# 40_Controles.net
KiCad netlist of a schematic drawn in Altium Designer
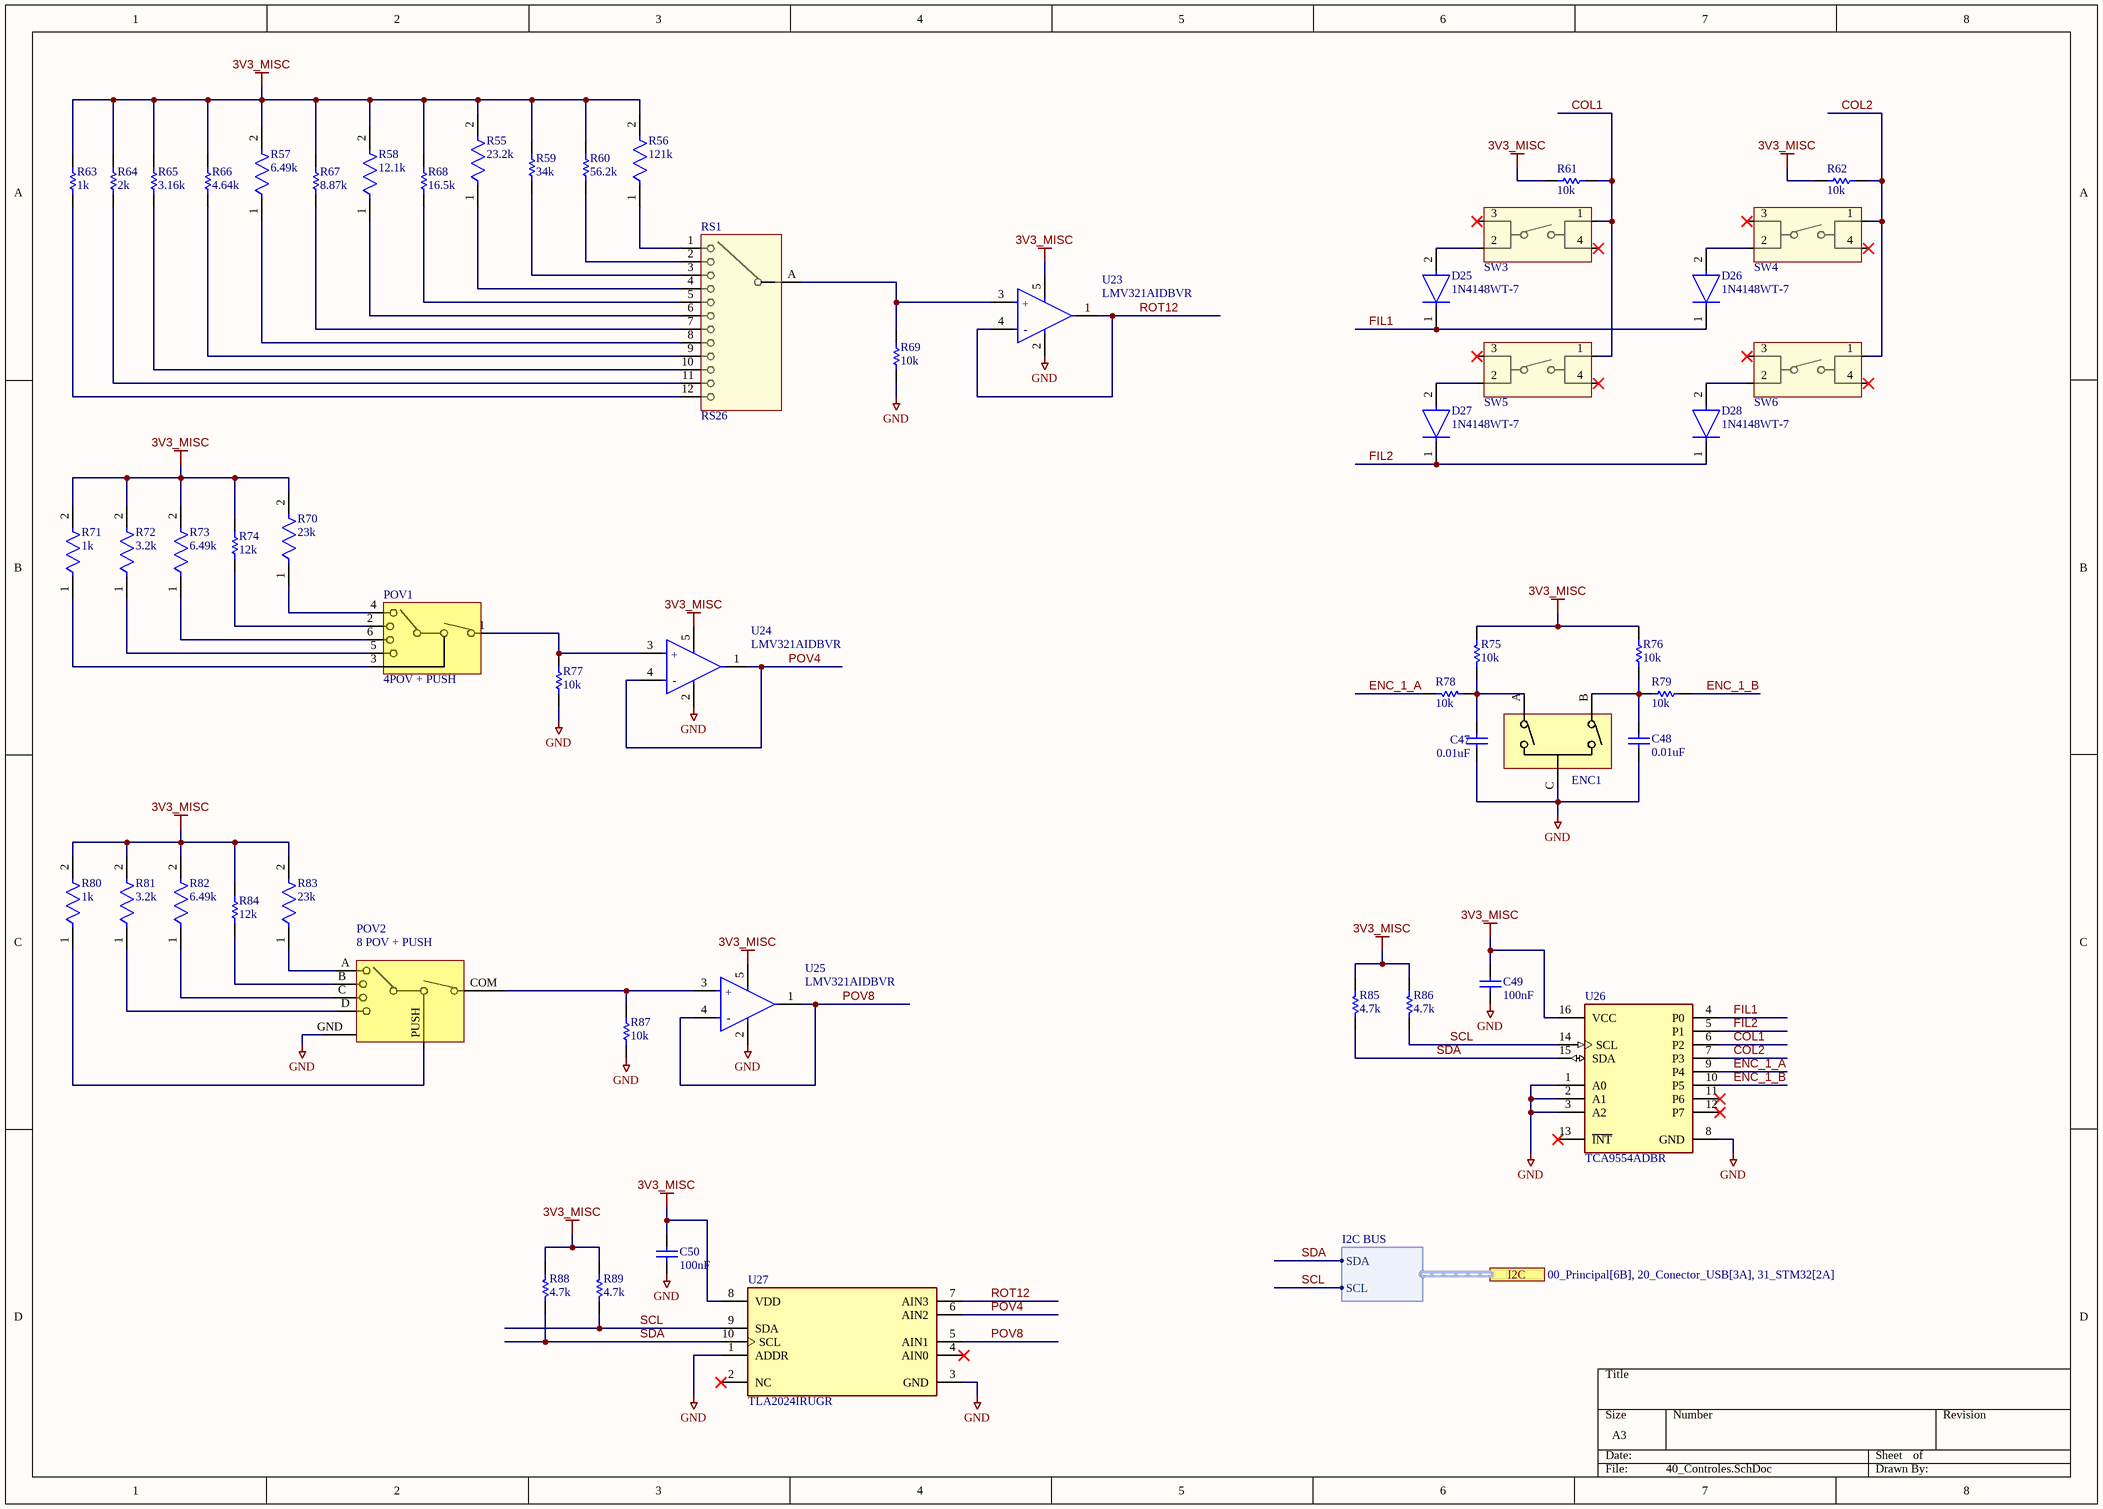
[diagram p0: 40_Controles.SchDoc]

(export (version "E")
  (design (tool "Eeschema 10.0.6"))
  (components
    (comp (ref "C47")
      (value "0.01uF")
      (footprint "CAPC1005X55X25LL05T10")
      (fields (field (name "MANUFACTURER") "Murata") (field (name "PART NUMBER") "GRM155R71E103KA01D"))
      (libsource (lib "Altium Content Vault") (part "CAP"))
    )
    (comp (ref "C48")
      (value "0.01uF")
      (footprint "CAPC1005X55X25LL05T10")
      (fields (field (name "MANUFACTURER") "Murata") (field (name "PART NUMBER") "GRM155R71E103KA01D"))
      (libsource (lib "Altium Content Vault") (part "CAP"))
    )
    (comp (ref "C49")
      (value "100nF")
      (footprint "CAPC1005X55X25NL05T05")
      (fields (field (name "MANUFACTURER") "Vitramon") (field (name "PART NUMBER") "VJ0402Y104KXJCW1BC"))
      (libsource (lib "Altium Content Vault") (part "CAP"))
    )
    (comp (ref "C50")
      (value "100nF")
      (footprint "CAPC1005X55X25NL05T05")
      (fields (field (name "MANUFACTURER") "Vitramon") (field (name "PART NUMBER") "VJ0402Y104KXJCW1BC"))
      (libsource (lib "Altium Content Vault") (part "CAP"))
    )
    (comp (ref "D25")
      (value "1N4148WT-7")
      (footprint "FP-SOD523-MFG")
      (description "DIODE GEN PURP 80V 125MA SOD523")
      (libsource (lib "Altium Content Vault") (part "d7152d700b627762746794eb795d46e"))
    )
    (comp (ref "D26")
      (value "1N4148WT-7")
      (footprint "FP-SOD523-MFG")
      (description "DIODE GEN PURP 80V 125MA SOD523")
      (libsource (lib "Altium Content Vault") (part "d7152d700b627762746794eb795d46e"))
    )
    (comp (ref "D27")
      (value "1N4148WT-7")
      (footprint "FP-SOD523-MFG")
      (description "DIODE GEN PURP 80V 125MA SOD523")
      (libsource (lib "Altium Content Vault") (part "d7152d700b627762746794eb795d46e"))
    )
    (comp (ref "D28")
      (value "1N4148WT-7")
      (footprint "FP-SOD523-MFG")
      (description "DIODE GEN PURP 80V 125MA SOD523")
      (libsource (lib "Altium Content Vault") (part "d7152d700b627762746794eb795d46e"))
    )
    (comp (ref "ENC1")
      (value "Encoder")
      (footprint "PEC09-2315F-N0015")
      (description "PEC09 PC Pin Quadrature (Incremental) 12 Mechanical Encoder 11.4mm 70C")
      (fields
        (field (name "MANUFACTURER") "Bourns")
        (field (name "MANUFACTURER PART NUMBER") "PEC09-2315F-N0015")
      )
      (libsource (lib "Esquemas") (part "PEC09-2315F-N0015"))
    )
    (comp (ref "POV1")
      (value "4POV + PUSH")
      (footprint "TSSJ 30")
      (description "SWITCH NAVIGATION 20MA 15V")
      (libsource (lib "Esquemas") (part "TSSJ 30"))
    )
    (comp (ref "POV2")
      (value "8 POV + PUSH")
      (footprint "RKJXM1015004")
      (description "8-directional Stick Switch (with Center-push Function) RKJXM Series")
      (libsource (lib "Esquemas") (part "RKJXM1015004"))
    )
    (comp (ref "R55")
      (value "23.2k")
      (footprint "FP-ERJ2R-MFG")
      (description "RES SMD 23.2K OHM 1% 1/10W 0402")
      (fields
        (field (name "MANUFACTURER PART NUMBER") "ERJ-2RKF2322X")
        (field (name "MANUFACTURER") "Panasonic")
      )
      (libsource (lib "Altium Content Vault") (part "1029c3af85768c4190bb7ad29bc67b5"))
    )
    (comp (ref "R56")
      (value "121k")
      (footprint "FP-ERJ2R-MFG")
      (description "RES SMD 121K OHM 1% 1/10W 0402")
      (fields
        (field (name "OCTOPART") "https://octopart.com/erj-2rkf1213x-panasonic-55420883")
        (field (name "MANUFACTURER") "Panasonic")
      )
      (libsource (lib "Altium Content Vault") (part "1029c3af85768c4190bb7ad29bc67b5"))
    )
    (comp (ref "R57")
      (value "6.49k")
      (footprint "FP-ERJ2RK-MFG")
      (fields (field (name "TOLERANCE") "1%"))
      (libsource (lib "Altium Content Vault") (part "1029c3af85768c4190bb7ad29bc67b5"))
    )
    (comp (ref "R58")
      (value "12.1k")
      (footprint "FP-ERJ2RK-IPC_C")
      (description "RES SMD 12.1K OHM 1% 1/10W 0402")
      (fields (field (name "TOLERANCE") "1%"))
      (libsource (lib "Altium Content Vault") (part "1029c3af85768c4190bb7ad29bc67b5"))
    )
    (comp (ref "R59")
      (value "34k")
      (footprint "RESC1005X40X25LL05T05")
      (fields (field (name "PART NUMBER") "ERJ-2RKF3402X") (field (name "MANUFACTURER") "Panasonic"))
      (libsource (lib "Altium Content Vault") (part "RES"))
    )
    (comp (ref "R60")
      (value "56.2k")
      (footprint "RESC1005X40X25LL05T05")
      (fields (field (name "PART NUMBER") "ERJ-2RKF5622X") (field (name "MANUFACTURER") "Panasonic"))
      (libsource (lib "Altium Content Vault") (part "RES"))
    )
    (comp (ref "R61")
      (value "10k")
      (footprint "RESC1005X40X25ML05T05")
      (fields (field (name "MANUFACTURER") "Panasonic") (field (name "PART NUMBER") "ERJ-2RHD1002X"))
      (libsource (lib "Altium Content Vault") (part "RES"))
    )
    (comp (ref "R62")
      (value "10k")
      (footprint "RESC1005X40X25ML05T05")
      (fields (field (name "MANUFACTURER") "Panasonic") (field (name "PART NUMBER") "ERJ-2RHD1002X"))
      (libsource (lib "Altium Content Vault") (part "RES"))
    )
    (comp (ref "R63")
      (value "1k")
      (footprint "RESC1005X40X25NL05T05")
      (description "Chip Resistor, 1 KOhm, +/- 1%, 100 mW, -55 to 155 degC, 0402 (1005 Metric), RoHS, Tape and Reel")
      (fields (field (name "PARTNUMBER") "ERJ-2RKF1001X") (field (name "MANUFACTURER") "Basic Passives"))
      (libsource (lib "Altium Content Vault") (part "RES-2"))
    )
    (comp (ref "R64")
      (value "2k")
      (footprint "RESC1005X40X25LL10T10")
      (fields (field (name "MANUFACTURER") "Panasonic") (field (name "PART NUMBER") "ERA-2AEB202X"))
      (libsource (lib "Altium Content Vault") (part "RES"))
    )
    (comp (ref "R65")
      (value "3.16k")
      (footprint "RESC1005X40X25ML05T05")
      (fields (field (name "MANUFACTURER") "Panasonic") (field (name "PART NUMBER") "ERJ-2RKF3161X"))
      (libsource (lib "Altium Content Vault") (part "RES"))
    )
    (comp (ref "R66")
      (value "4.64k")
      (footprint "RESC1005X40X25LL05T05")
      (fields (field (name "PART NUMBER") "ERJ-2RKF4641X") (field (name "MANUFACTURER") "Panasonic"))
      (libsource (lib "Altium Content Vault") (part "RES"))
    )
    (comp (ref "R67")
      (value "8.87k")
      (footprint "RESC1005X40X25NL05T05")
      (fields (field (name "PART NUMBER") "ERJ-2RKF8871X") (field (name "MANUFACTURER") "Panasonic"))
      (libsource (lib "Altium Content Vault") (part "RES"))
    )
    (comp (ref "R68")
      (value "16.5k")
      (footprint "RESC1005X40X25LL05T05")
      (fields (field (name "PART NUMBER") "ERJ-2RKF1652X") (field (name "MANUFACTURER") "Panasonic"))
      (libsource (lib "Altium Content Vault") (part "RES"))
    )
    (comp (ref "R69")
      (value "10k")
      (footprint "RESC1005X40X25ML05T05")
      (fields (field (name "MANUFACTURER") "Panasonic") (field (name "PART NUMBER") "ERJ-2RHD1002X"))
      (libsource (lib "Altium Content Vault") (part "RES"))
    )
    (comp (ref "R70")
      (value "23k")
      (footprint "FP-AC0402-MFG")
      (description "RES 23.2kΩ ±1% 0.063W 0402")
      (fields (field (name "TOLERANCE") "1%"))
      (libsource (lib "Altium Content Vault") (part "1029c3af85768c4190bb7ad29bc67b5"))
    )
    (comp (ref "R71")
      (value "1k")
      (footprint "FP-MCS0402-IPC_B")
      (description "RES SMD 1.2K OHM 1% 1/10W 0402")
      (fields (field (name "TOLERANCE") "0.1%"))
      (libsource (lib "Altium Content Vault") (part "1029c3af85768c4190bb7ad29bc67b5"))
    )
    (comp (ref "R72")
      (value "3.2k")
      (footprint "FP-RN73R1E-IPC_A")
      (description "3.2kΩ ±0.1% 0.063W, 1/16W Chip Resistor 0402 (1005 Metric) Moisture Resistant Thin Film")
      (libsource (lib "Altium Content Vault") (part "1029c3af85768c4190bb7ad29bc67b5"))
    )
    (comp (ref "R73")
      (value "6.49k")
      (footprint "FP-MCS0402-IPC_A")
      (description "RES SMD 1.2K OHM 1% 1/10W 0402")
      (fields (field (name "TOLERANCE") "1%"))
      (libsource (lib "Altium Content Vault") (part "1029c3af85768c4190bb7ad29bc67b5"))
    )
    (comp (ref "R74")
      (value "12k")
      (footprint "RESC0402(1005)_M")
      (description "12K 0.063W 5% 0402 (1005 Metric)  SMD")
      (fields (field (name "TOLERANCE") "5 %") (field (name "POWER") "0.063 W"))
      (libsource (lib "Altium Content Vault") (part "RES"))
    )
    (comp (ref "R75")
      (value "10k")
      (footprint "RESC1005X40X25ML05T05")
      (fields (field (name "MANUFACTURER") "Panasonic") (field (name "PART NUMBER") "ERJ-2RHD1002X"))
      (libsource (lib "Altium Content Vault") (part "RES"))
    )
    (comp (ref "R76")
      (value "10k")
      (footprint "RESC1005X40X25ML05T05")
      (fields (field (name "MANUFACTURER") "Panasonic") (field (name "PART NUMBER") "ERJ-2RHD1002X"))
      (libsource (lib "Altium Content Vault") (part "RES"))
    )
    (comp (ref "R77")
      (value "10k")
      (footprint "RESC1005X40X25ML05T05")
      (fields (field (name "MANUFACTURER") "Panasonic") (field (name "PART NUMBER") "ERJ-2RHD1002X"))
      (libsource (lib "Altium Content Vault") (part "RES"))
    )
    (comp (ref "R78")
      (value "10k")
      (footprint "RESC1005X40X25ML05T05")
      (fields (field (name "MANUFACTURER") "Panasonic") (field (name "PART NUMBER") "ERJ-2RHD1002X"))
      (libsource (lib "Altium Content Vault") (part "RES"))
    )
    (comp (ref "R79")
      (value "10k")
      (footprint "RESC1005X40X25ML05T05")
      (fields (field (name "MANUFACTURER") "Panasonic") (field (name "PART NUMBER") "ERJ-2RHD1002X"))
      (libsource (lib "Altium Content Vault") (part "RES"))
    )
    (comp (ref "R80")
      (value "1k")
      (footprint "FP-MCS0402-IPC_B")
      (description "RES SMD 1.2K OHM 1% 1/10W 0402")
      (fields (field (name "TOLERANCE") "0.1%"))
      (libsource (lib "Altium Content Vault") (part "1029c3af85768c4190bb7ad29bc67b5"))
    )
    (comp (ref "R81")
      (value "3.2k")
      (footprint "FP-RN73R1E-IPC_A")
      (description "3.2kΩ ±0.1% 0.063W, 1/16W Chip Resistor 0402 (1005 Metric) Moisture Resistant Thin Film")
      (libsource (lib "Altium Content Vault") (part "1029c3af85768c4190bb7ad29bc67b5"))
    )
    (comp (ref "R82")
      (value "6.49k")
      (footprint "FP-MCS0402-IPC_A")
      (description "RES SMD 1.2K OHM 1% 1/10W 0402")
      (fields (field (name "TOLERANCE") "1%"))
      (libsource (lib "Altium Content Vault") (part "1029c3af85768c4190bb7ad29bc67b5"))
    )
    (comp (ref "R83")
      (value "23k")
      (footprint "FP-AC0402-MFG")
      (description "RES 23.2kΩ ±1% 0.063W 0402")
      (fields (field (name "TOLERANCE") "1%"))
      (libsource (lib "Altium Content Vault") (part "1029c3af85768c4190bb7ad29bc67b5"))
    )
    (comp (ref "R84")
      (value "12k")
      (footprint "RESC0402(1005)_M")
      (description "12K 0.063W 5% 0402 (1005 Metric)  SMD")
      (fields (field (name "TOLERANCE") "5 %") (field (name "POWER") "0.063 W"))
      (libsource (lib "Altium Content Vault") (part "RES"))
    )
    (comp (ref "R85")
      (value "4.7k")
      (footprint "RESC1005X40X25ML05T10")
      (fields (field (name "MANUFACTURER") "Panasonic") (field (name "PART NUMBER") "ERJ-S02F4701X"))
      (libsource (lib "Altium Content Vault") (part "RES"))
    )
    (comp (ref "R86")
      (value "4.7k")
      (footprint "RESC1005X40X25ML05T10")
      (fields (field (name "MANUFACTURER") "Panasonic") (field (name "PART NUMBER") "ERJ-S02F4701X"))
      (libsource (lib "Altium Content Vault") (part "RES"))
    )
    (comp (ref "R87")
      (value "10k")
      (footprint "RESC1005X40X25ML05T05")
      (fields (field (name "MANUFACTURER") "Panasonic") (field (name "PART NUMBER") "ERJ-2RHD1002X"))
      (libsource (lib "Altium Content Vault") (part "RES"))
    )
    (comp (ref "R88")
      (value "4.7k")
      (footprint "RESC1005X40X25ML05T10")
      (fields (field (name "MANUFACTURER") "Panasonic") (field (name "PART NUMBER") "ERJ-S02F4701X"))
      (libsource (lib "Altium Content Vault") (part "RES"))
    )
    (comp (ref "R89")
      (value "4.7k")
      (footprint "RESC1005X40X25ML05T10")
      (fields (field (name "MANUFACTURER") "Panasonic") (field (name "PART NUMBER") "ERJ-S02F4701X"))
      (libsource (lib "Altium Content Vault") (part "RES"))
    )
    (comp (ref "RS1")
      (value "RS26")
      (footprint "RS26")
      (description "RS26 Rotary Type Band Switch Position Switch")
      (libsource (lib "Esquemas") (part "RS26 Rotary Coder"))
    )
    (comp (ref "SW3")
      (value "KSC441G70SHLFSPF")
      (footprint "KSC441G 70SH LFS PF")
      (description "Switch Tactile N.O. SPST Button 1VA 32VDC 50mA 4N Gull Wing SMD T/R")
      (fields (field (name "MANUFACTURER") "C&K Components"))
      (libsource (lib "Esquemas") (part "KSC441G70SHLFSPF"))
    )
    (comp (ref "SW4")
      (value "KSC441G70SHLFSPF")
      (footprint "KSC441G 70SH LFS PF")
      (description "Switch Tactile N.O. SPST Button 1VA 32VDC 50mA 4N Gull Wing SMD T/R")
      (fields (field (name "MANUFACTURER") "C&K Components"))
      (libsource (lib "Esquemas") (part "KSC441G70SHLFSPF"))
    )
    (comp (ref "SW5")
      (value "KSC441G70SHLFSPF")
      (footprint "KSC441G 70SH LFS PF")
      (description "Switch Tactile N.O. SPST Button 1VA 32VDC 50mA 4N Gull Wing SMD T/R")
      (fields (field (name "MANUFACTURER") "C&K Components"))
      (libsource (lib "Esquemas") (part "KSC441G70SHLFSPF"))
    )
    (comp (ref "SW6")
      (value "KSC441G70SHLFSPF")
      (footprint "KSC441G 70SH LFS PF")
      (description "Switch Tactile N.O. SPST Button 1VA 32VDC 50mA 4N Gull Wing SMD T/R")
      (fields (field (name "MANUFACTURER") "C&K Components"))
      (libsource (lib "Esquemas") (part "KSC441G70SHLFSPF"))
    )
    (comp (ref "U23")
      (value "LMV321AIDBVR")
      (footprint "FP-DBV0005A-MFG")
      (description "IC OPAMP GP 1 CIRCUIT SOT23-5")
      (libsource (lib "Altium Content Vault") (part "1dcd28e651784f0a5a8ed6f8452eeff"))
    )
    (comp (ref "U24")
      (value "LMV321AIDBVR")
      (footprint "FP-DBV0005A-MFG")
      (description "IC OPAMP GP 1 CIRCUIT SOT23-5")
      (libsource (lib "Altium Content Vault") (part "1dcd28e651784f0a5a8ed6f8452eeff"))
    )
    (comp (ref "U25")
      (value "LMV321AIDBVR")
      (footprint "FP-DBV0005A-MFG")
      (description "IC OPAMP GP 1 CIRCUIT SOT23-5")
      (libsource (lib "Altium Content Vault") (part "1dcd28e651784f0a5a8ed6f8452eeff"))
    )
    (comp (ref "U26")
      (value "TCA9554ADBR")
      (footprint "FP-DB0016A-MFG")
      (description "IC SMBUS I/O EXPANDER I2C 16SSOP")
      (libsource (lib "Altium Content Vault") (part "5b8be9e160fc3a406f4826644c42a9b"))
    )
    (comp (ref "U27")
      (value "TLA2024IRUGR")
      (footprint "FP-RUG0010A-MFG")
      (description "IC ADC 12BIT SIGMA-DELTA 10X2QFN")
      (libsource (lib "Altium Content Vault") (part "eb3f1feaf096e0a4fed058628c4118d"))
    )
  )
  (nets
    (net (code "3") (name "/COL1") (class "Default")
      (node (ref "R61") (pin "1") (pinfunction "1_1") (pintype "passive"))
      (node (ref "SW3") (pin "1") (pinfunction "0_1") (pintype "passive"))
      (node (ref "SW5") (pin "1") (pinfunction "0_1") (pintype "passive"))
      (node (ref "U26") (pin "6") (pinfunction "P2_6") (pintype "passive"))
    )
    (net (code "4") (name "/COL2") (class "Default")
      (node (ref "R62") (pin "1") (pinfunction "1_1") (pintype "passive"))
      (node (ref "SW4") (pin "1") (pinfunction "0_1") (pintype "passive"))
      (node (ref "SW6") (pin "1") (pinfunction "0_1") (pintype "passive"))
      (node (ref "U26") (pin "7") (pinfunction "P3_7") (pintype "passive"))
    )
    (net (code "5") (name "/ENC_1_A") (class "Default")
      (node (ref "R78") (pin "1") (pinfunction "1_1") (pintype "passive"))
      (node (ref "U26") (pin "9") (pinfunction "P4_9") (pintype "passive"))
    )
    (net (code "6") (name "/ENC_1_B") (class "Default")
      (node (ref "R79") (pin "1") (pinfunction "1_1") (pintype "passive"))
      (node (ref "U26") (pin "10") (pinfunction "P5_10") (pintype "passive"))
    )
    (net (code "7") (name "/FIL1") (class "Default")
      (node (ref "D25") (pin "1") (pinfunction "C_1") (pintype "passive"))
      (node (ref "D26") (pin "1") (pinfunction "C_1") (pintype "passive"))
      (node (ref "U26") (pin "4") (pinfunction "P0_4") (pintype "passive"))
    )
    (net (code "8") (name "/FIL2") (class "Default")
      (node (ref "D27") (pin "1") (pinfunction "C_1") (pintype "passive"))
      (node (ref "D28") (pin "1") (pinfunction "C_1") (pintype "passive"))
      (node (ref "U26") (pin "5") (pinfunction "P1_5") (pintype "passive"))
    )
    (net (code "9") (name "/POV4") (class "Default")
      (node (ref "U24") (pin "1") (pinfunction "OUT_1") (pintype "passive"))
      (node (ref "U24") (pin "4") (pinfunction "-IN_4") (pintype "tri_state"))
      (node (ref "U27") (pin "6") (pinfunction "AIN2_6") (pintype "passive"))
    )
    (net (code "10") (name "/POV8") (class "Default")
      (node (ref "U25") (pin "1") (pinfunction "OUT_1") (pintype "passive"))
      (node (ref "U25") (pin "4") (pinfunction "-IN_4") (pintype "tri_state"))
      (node (ref "U27") (pin "5") (pinfunction "AIN1_5") (pintype "passive"))
    )
    (net (code "11") (name "/ROT12") (class "Default")
      (node (ref "U23") (pin "1") (pinfunction "OUT_1") (pintype "passive"))
      (node (ref "U23") (pin "4") (pinfunction "-IN_4") (pintype "tri_state"))
      (node (ref "U27") (pin "7") (pinfunction "AIN3_7") (pintype "passive"))
    )
    (net (code "12") (name "/SCL") (class "Default")
      (node (ref "R86") (pin "1") (pinfunction "1_1") (pintype "passive"))
      (node (ref "R89") (pin "1") (pinfunction "1_1") (pintype "passive"))
      (node (ref "U26") (pin "14") (pinfunction "SCL_14") (pintype "input"))
      (node (ref "U27") (pin "9") (pinfunction "SDA_9") (pintype "passive"))
    )
    (net (code "13") (name "/SDA") (class "Default")
      (node (ref "R85") (pin "1") (pinfunction "1_1") (pintype "passive"))
      (node (ref "R88") (pin "1") (pinfunction "1_1") (pintype "passive"))
      (node (ref "U26") (pin "15") (pinfunction "SDA_15") (pintype "bidirectional"))
      (node (ref "U27") (pin "10") (pinfunction "SCL_10") (pintype "passive"))
    )
    (net (code "15") (name "3V3_MISC") (class "Default")
      (node (ref "C49") (pin "2") (pinfunction "2_2") (pintype "passive"))
      (node (ref "C50") (pin "2") (pinfunction "2_2") (pintype "passive"))
      (node (ref "R55") (pin "2") (pinfunction "2_2") (pintype "passive"))
      (node (ref "R56") (pin "2") (pinfunction "2_2") (pintype "passive"))
      (node (ref "R57") (pin "2") (pinfunction "2_2") (pintype "passive"))
      (node (ref "R58") (pin "2") (pinfunction "2_2") (pintype "passive"))
      (node (ref "R59") (pin "2") (pinfunction "2_2") (pintype "passive"))
      (node (ref "R60") (pin "2") (pinfunction "2_2") (pintype "passive"))
      (node (ref "R61") (pin "2") (pinfunction "2_2") (pintype "passive"))
      (node (ref "R62") (pin "2") (pinfunction "2_2") (pintype "passive"))
      (node (ref "R63") (pin "2") (pinfunction "2_2") (pintype "passive"))
      (node (ref "R64") (pin "2") (pinfunction "2_2") (pintype "passive"))
      (node (ref "R65") (pin "2") (pinfunction "2_2") (pintype "passive"))
      (node (ref "R66") (pin "2") (pinfunction "2_2") (pintype "passive"))
      (node (ref "R67") (pin "2") (pinfunction "2_2") (pintype "passive"))
      (node (ref "R68") (pin "2") (pinfunction "2_2") (pintype "passive"))
      (node (ref "R70") (pin "2") (pinfunction "2_2") (pintype "passive"))
      (node (ref "R71") (pin "2") (pinfunction "2_2") (pintype "passive"))
      (node (ref "R72") (pin "2") (pinfunction "2_2") (pintype "passive"))
      (node (ref "R73") (pin "2") (pinfunction "2_2") (pintype "passive"))
      (node (ref "R74") (pin "2") (pinfunction "2_2") (pintype "passive"))
      (node (ref "R75") (pin "1") (pinfunction "1_1") (pintype "passive"))
      (node (ref "R76") (pin "1") (pinfunction "1_1") (pintype "passive"))
      (node (ref "R80") (pin "2") (pinfunction "2_2") (pintype "passive"))
      (node (ref "R81") (pin "2") (pinfunction "2_2") (pintype "passive"))
      (node (ref "R82") (pin "2") (pinfunction "2_2") (pintype "passive"))
      (node (ref "R83") (pin "2") (pinfunction "2_2") (pintype "passive"))
      (node (ref "R84") (pin "2") (pinfunction "2_2") (pintype "passive"))
      (node (ref "R85") (pin "2") (pinfunction "2_2") (pintype "passive"))
      (node (ref "R86") (pin "2") (pinfunction "2_2") (pintype "passive"))
      (node (ref "R88") (pin "2") (pinfunction "2_2") (pintype "passive"))
      (node (ref "R89") (pin "2") (pinfunction "2_2") (pintype "passive"))
      (node (ref "U23") (pin "5") (pinfunction "V+_5") (pintype "passive"))
      (node (ref "U24") (pin "5") (pinfunction "V+_5") (pintype "passive"))
      (node (ref "U25") (pin "5") (pinfunction "V+_5") (pintype "passive"))
      (node (ref "U26") (pin "16") (pinfunction "VCC_16") (pintype "passive"))
      (node (ref "U27") (pin "8") (pinfunction "VDD_8") (pintype "passive"))
    )
    (net (code "16") (name "GND") (class "Default")
      (node (ref "C47") (pin "1") (pinfunction "1_1") (pintype "passive"))
      (node (ref "C48") (pin "1") (pinfunction "1_1") (pintype "passive"))
      (node (ref "C49") (pin "1") (pinfunction "1_1") (pintype "passive"))
      (node (ref "C50") (pin "1") (pinfunction "1_1") (pintype "passive"))
      (node (ref "ENC1") (pin "C") (pinfunction "COM_C") (pintype "passive"))
      (node (ref "POV2") (pin "GND") (pinfunction "GND_GND") (pintype "passive"))
      (node (ref "R69") (pin "1") (pinfunction "1_1") (pintype "passive"))
      (node (ref "R77") (pin "1") (pinfunction "1_1") (pintype "passive"))
      (node (ref "R87") (pin "1") (pinfunction "1_1") (pintype "passive"))
      (node (ref "U23") (pin "2") (pinfunction "V-_2") (pintype "passive"))
      (node (ref "U24") (pin "2") (pinfunction "V-_2") (pintype "passive"))
      (node (ref "U25") (pin "2") (pinfunction "V-_2") (pintype "passive"))
      (node (ref "U26") (pin "1") (pinfunction "A0_1") (pintype "passive"))
      (node (ref "U26") (pin "2") (pinfunction "A1_2") (pintype "passive"))
      (node (ref "U26") (pin "3") (pinfunction "A2_3") (pintype "passive"))
      (node (ref "U26") (pin "8") (pinfunction "GND_8") (pintype "passive"))
      (node (ref "U27") (pin "1") (pinfunction "ADDR_1") (pintype "passive"))
      (node (ref "U27") (pin "3") (pinfunction "GND_3") (pintype "passive"))
    )
    (net (code "17") (name "Net-(C47-Pad2)") (class "Default")
      (node (ref "C47") (pin "2") (pinfunction "2_2") (pintype "passive"))
      (node (ref "ENC1") (pin "A") (pinfunction "COM_A") (pintype "passive"))
      (node (ref "R75") (pin "2") (pinfunction "2_2") (pintype "passive"))
      (node (ref "R78") (pin "2") (pinfunction "2_2") (pintype "passive"))
    )
    (net (code "18") (name "Net-(C48-Pad2)") (class "Default")
      (node (ref "C48") (pin "2") (pinfunction "2_2") (pintype "passive"))
      (node (ref "ENC1") (pin "B") (pinfunction "COM_B") (pintype "passive"))
      (node (ref "R76") (pin "2") (pinfunction "2_2") (pintype "passive"))
      (node (ref "R79") (pin "2") (pinfunction "2_2") (pintype "passive"))
    )
    (net (code "19") (name "Net-(D25-A)") (class "Default")
      (node (ref "D25") (pin "2") (pinfunction "A_2") (pintype "passive"))
      (node (ref "SW3") (pin "2") (pinfunction "1_2") (pintype "passive"))
    )
    (net (code "20") (name "Net-(D26-A)") (class "Default")
      (node (ref "D26") (pin "2") (pinfunction "A_2") (pintype "passive"))
      (node (ref "SW4") (pin "2") (pinfunction "1_2") (pintype "passive"))
    )
    (net (code "21") (name "Net-(D27-A)") (class "Default")
      (node (ref "D27") (pin "2") (pinfunction "A_2") (pintype "passive"))
      (node (ref "SW5") (pin "2") (pinfunction "1_2") (pintype "passive"))
    )
    (net (code "22") (name "Net-(D28-A)") (class "Default")
      (node (ref "D28") (pin "2") (pinfunction "A_2") (pintype "passive"))
      (node (ref "SW6") (pin "2") (pinfunction "1_2") (pintype "passive"))
    )
    (net (code "23") (name "Net-(POV1-4)") (class "Default")
      (node (ref "POV1") (pin "3") (pinfunction "4_3") (pintype "passive"))
      (node (ref "R71") (pin "1") (pinfunction "1_1") (pintype "passive"))
    )
    (net (code "24") (name "Net-(POV1-COM)") (class "Default")
      (node (ref "POV1") (pin "1") (pinfunction "COM_1") (pintype "passive"))
      (node (ref "R77") (pin "2") (pinfunction "2_2") (pintype "passive"))
      (node (ref "U24") (pin "3") (pinfunction "+IN_3") (pintype "tri_state"))
    )
    (net (code "25") (name "Net-(POV1-DIRA)") (class "Default")
      (node (ref "POV1") (pin "4") (pinfunction "DIRA_4") (pintype "passive"))
      (node (ref "R70") (pin "1") (pinfunction "1_1") (pintype "passive"))
    )
    (net (code "26") (name "Net-(POV1-DIRB)") (class "Default")
      (node (ref "POV1") (pin "2") (pinfunction "DIRB_2") (pintype "passive"))
      (node (ref "R74") (pin "1") (pinfunction "1_1") (pintype "passive"))
    )
    (net (code "27") (name "Net-(POV1-DIRC)") (class "Default")
      (node (ref "POV1") (pin "6") (pinfunction "DIRC_6") (pintype "passive"))
      (node (ref "R73") (pin "1") (pinfunction "1_1") (pintype "passive"))
    )
    (net (code "28") (name "Net-(POV1-DIRD)") (class "Default")
      (node (ref "POV1") (pin "5") (pinfunction "DIRD_5") (pintype "passive"))
      (node (ref "R72") (pin "1") (pinfunction "1_1") (pintype "passive"))
    )
    (net (code "29") (name "Net-(POV2-DIRA)") (class "Default")
      (node (ref "POV2") (pin "A") (pinfunction "DIRA_A") (pintype "passive"))
      (node (ref "R83") (pin "1") (pinfunction "1_1") (pintype "passive"))
    )
    (net (code "30") (name "Net-(POV2-DIRB)") (class "Default")
      (node (ref "POV2") (pin "B") (pinfunction "DIRB_B") (pintype "passive"))
      (node (ref "R84") (pin "1") (pinfunction "1_1") (pintype "passive"))
    )
    (net (code "31") (name "Net-(POV2-DIRC)") (class "Default")
      (node (ref "POV2") (pin "C") (pinfunction "DIRC_C") (pintype "passive"))
      (node (ref "R82") (pin "1") (pinfunction "1_1") (pintype "passive"))
    )
    (net (code "32") (name "Net-(POV2-DIRD)") (class "Default")
      (node (ref "POV2") (pin "D") (pinfunction "DIRD_D") (pintype "passive"))
      (node (ref "R81") (pin "1") (pinfunction "1_1") (pintype "passive"))
    )
    (net (code "33") (name "Net-(POV2-PadPUSH)") (class "Default")
      (node (ref "POV2") (pin "PUSH") (pinfunction "PUSH_PUSH") (pintype "passive"))
      (node (ref "R80") (pin "1") (pinfunction "1_1") (pintype "passive"))
    )
    (net (code "34") (name "Net-(R55-Pad1)") (class "Default")
      (node (ref "R55") (pin "1") (pinfunction "1_1") (pintype "passive"))
      (node (ref "RS1") (pin "4") (pinfunction "A_4") (pintype "passive"))
    )
    (net (code "35") (name "Net-(R56-Pad1)") (class "Default")
      (node (ref "R56") (pin "1") (pinfunction "1_1") (pintype "passive"))
      (node (ref "RS1") (pin "1") (pinfunction "A_1") (pintype "passive"))
    )
    (net (code "36") (name "Net-(R57-Pad1)") (class "Default")
      (node (ref "R57") (pin "1") (pinfunction "1_1") (pintype "passive"))
      (node (ref "RS1") (pin "8") (pinfunction "A_8") (pintype "passive"))
    )
    (net (code "37") (name "Net-(R58-Pad1)") (class "Default")
      (node (ref "R58") (pin "1") (pinfunction "1_1") (pintype "passive"))
      (node (ref "RS1") (pin "6") (pinfunction "A_6") (pintype "passive"))
    )
    (net (code "38") (name "Net-(R59-Pad1)") (class "Default")
      (node (ref "R59") (pin "1") (pinfunction "1_1") (pintype "passive"))
      (node (ref "RS1") (pin "3") (pinfunction "A_3") (pintype "passive"))
    )
    (net (code "39") (name "Net-(R60-Pad1)") (class "Default")
      (node (ref "R60") (pin "1") (pinfunction "1_1") (pintype "passive"))
      (node (ref "RS1") (pin "2") (pinfunction "A_2") (pintype "passive"))
    )
    (net (code "40") (name "Net-(R63-Pad1)") (class "Default")
      (node (ref "R63") (pin "1") (pinfunction "1_1") (pintype "passive"))
      (node (ref "RS1") (pin "12") (pinfunction "A_12") (pintype "passive"))
    )
    (net (code "41") (name "Net-(R64-Pad1)") (class "Default")
      (node (ref "R64") (pin "1") (pinfunction "1_1") (pintype "passive"))
      (node (ref "RS1") (pin "11") (pinfunction "A_11") (pintype "passive"))
    )
    (net (code "42") (name "Net-(R65-Pad1)") (class "Default")
      (node (ref "R65") (pin "1") (pinfunction "1_1") (pintype "passive"))
      (node (ref "RS1") (pin "10") (pinfunction "A_10") (pintype "passive"))
    )
    (net (code "43") (name "Net-(R66-Pad1)") (class "Default")
      (node (ref "R66") (pin "1") (pinfunction "1_1") (pintype "passive"))
      (node (ref "RS1") (pin "9") (pinfunction "A_9") (pintype "passive"))
    )
    (net (code "44") (name "Net-(R67-Pad1)") (class "Default")
      (node (ref "R67") (pin "1") (pinfunction "1_1") (pintype "passive"))
      (node (ref "RS1") (pin "7") (pinfunction "A_7") (pintype "passive"))
    )
    (net (code "45") (name "Net-(R68-Pad1)") (class "Default")
      (node (ref "R68") (pin "1") (pinfunction "1_1") (pintype "passive"))
      (node (ref "RS1") (pin "5") (pinfunction "A_5") (pintype "passive"))
    )
    (net (code "46") (name "Net-(U23-+IN)") (class "Default")
      (node (ref "R69") (pin "2") (pinfunction "2_2") (pintype "passive"))
      (node (ref "RS1") (pin "A") (pintype "passive"))
      (node (ref "U23") (pin "3") (pinfunction "+IN_3") (pintype "tri_state"))
    )
    (net (code "47") (name "Net-(U25-+IN)") (class "Default")
      (node (ref "POV2") (pin "COM") (pinfunction "COM_COM") (pintype "passive"))
      (node (ref "R87") (pin "2") (pinfunction "2_2") (pintype "passive"))
      (node (ref "U25") (pin "3") (pinfunction "+IN_3") (pintype "tri_state"))
    )
    (net (code "48") (name "unconnected-(SW3-2-Pad3)") (class "Default")
      (node (ref "SW3") (pin "3") (pinfunction "2_3") (pintype "passive+no_connect"))
    )
    (net (code "49") (name "unconnected-(SW3-3-Pad4)") (class "Default")
      (node (ref "SW3") (pin "4") (pinfunction "3_4") (pintype "passive+no_connect"))
    )
    (net (code "50") (name "unconnected-(SW4-2-Pad3)") (class "Default")
      (node (ref "SW4") (pin "3") (pinfunction "2_3") (pintype "passive+no_connect"))
    )
    (net (code "51") (name "unconnected-(SW4-3-Pad4)") (class "Default")
      (node (ref "SW4") (pin "4") (pinfunction "3_4") (pintype "passive+no_connect"))
    )
    (net (code "52") (name "unconnected-(SW5-2-Pad3)") (class "Default")
      (node (ref "SW5") (pin "3") (pinfunction "2_3") (pintype "passive+no_connect"))
    )
    (net (code "53") (name "unconnected-(SW5-3-Pad4)") (class "Default")
      (node (ref "SW5") (pin "4") (pinfunction "3_4") (pintype "passive+no_connect"))
    )
    (net (code "54") (name "unconnected-(SW6-2-Pad3)") (class "Default")
      (node (ref "SW6") (pin "3") (pinfunction "2_3") (pintype "passive+no_connect"))
    )
    (net (code "55") (name "unconnected-(SW6-3-Pad4)") (class "Default")
      (node (ref "SW6") (pin "4") (pinfunction "3_4") (pintype "passive+no_connect"))
    )
    (net (code "56") (name "unconnected-(U26-P6-Pad11)") (class "Default")
      (node (ref "U26") (pin "11") (pinfunction "P6_11") (pintype "passive+no_connect"))
    )
    (net (code "57") (name "unconnected-(U26-P7-Pad12)") (class "Default")
      (node (ref "U26") (pin "12") (pinfunction "P7_12") (pintype "passive+no_connect"))
    )
    (net (code "58") (name "unconnected-(U26-~{INT}-Pad13)") (class "Default")
      (node (ref "U26") (pin "13") (pinfunction "~{INT}_13") (pintype "open_collector+no_connect"))
    )
    (net (code "59") (name "unconnected-(U27-AIN0-Pad4)") (class "Default")
      (node (ref "U27") (pin "4") (pinfunction "AIN0_4") (pintype "passive+no_connect"))
    )
    (net (code "60") (name "unconnected-(U27-NC-Pad2)") (class "Default")
      (node (ref "U27") (pin "2") (pinfunction "NC_2") (pintype "passive+no_connect"))
    )
  )
)
